# CorruptCore.net
KiCad netlist of a schematic drawn in EAGLE
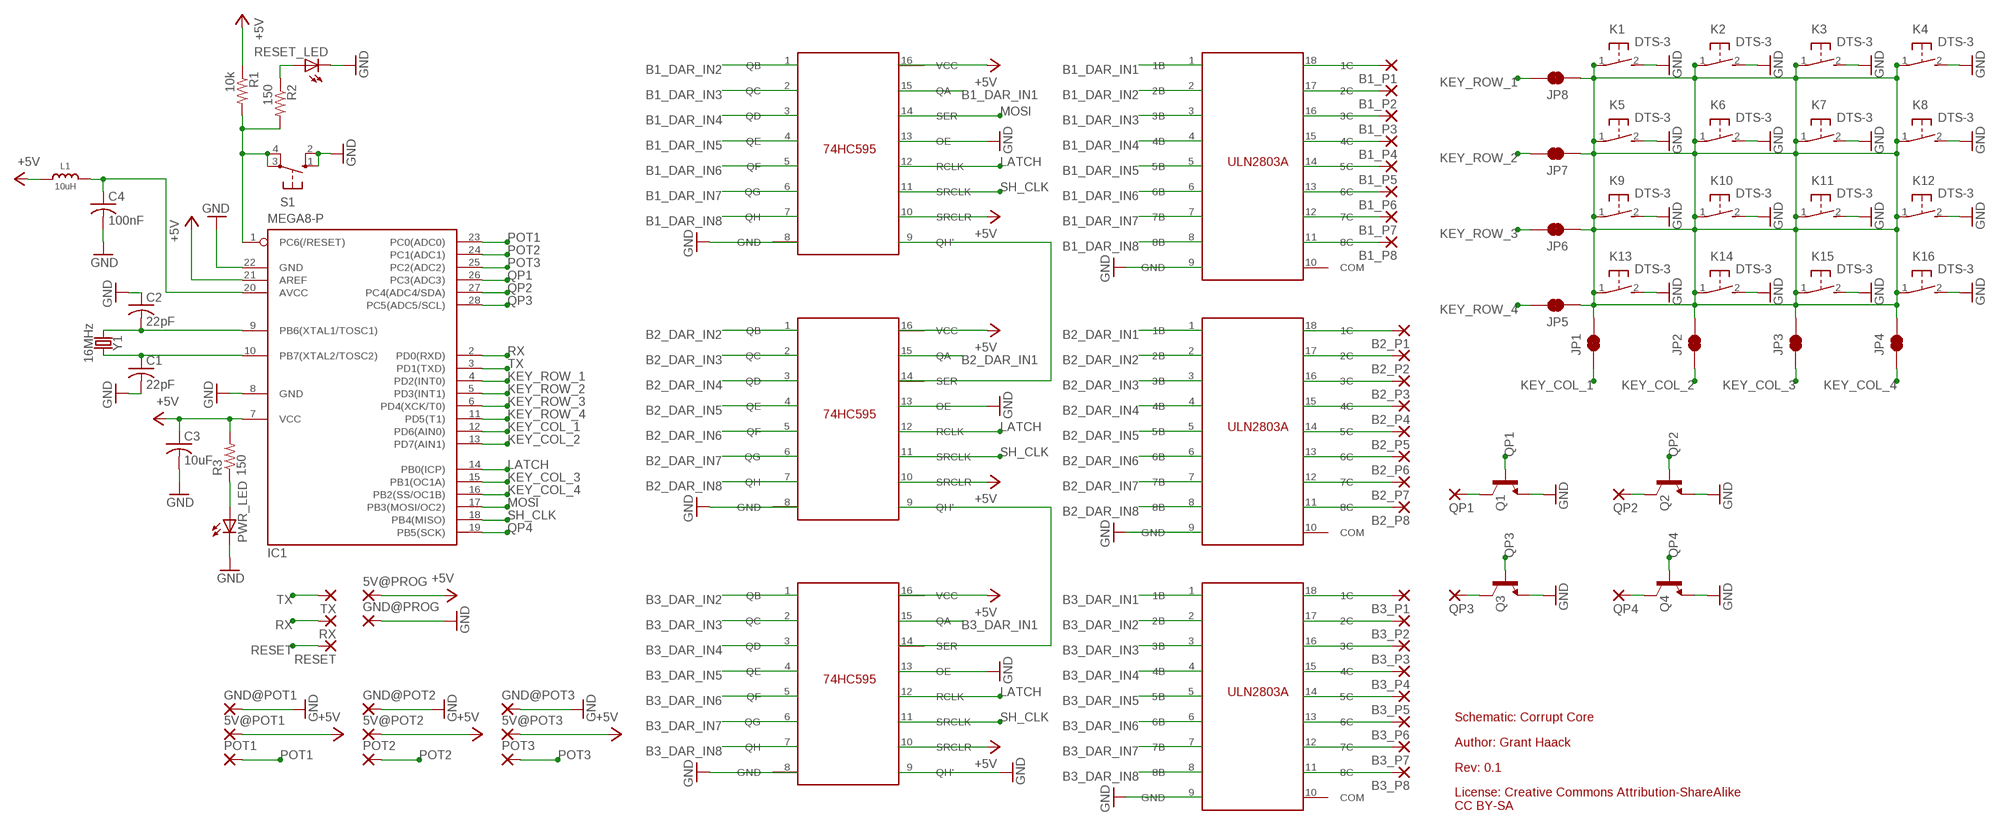
[diagram p0: schematic, sheet 1]

(export (version "E")
  (design (tool "Eeschema 10.0.6"))
  (components
    (comp (ref "5V@POT1")
      (value "2,54/1,1")
      (footprint "eagle-import:2,54_1,1")
      (libsource (lib "eagle-import") (part "2,54/1,1"))
    )
    (comp (ref "5V@POT2")
      (value "2,54/1,1")
      (footprint "eagle-import:2,54_1,1")
      (libsource (lib "eagle-import") (part "2,54/1,1"))
    )
    (comp (ref "5V@POT3")
      (value "2,54/1,1")
      (footprint "eagle-import:2,54_1,1")
      (libsource (lib "eagle-import") (part "2,54/1,1"))
    )
    (comp (ref "5V@PROG")
      (value "2,54/1,1")
      (footprint "eagle-import:2,54_1,1")
      (libsource (lib "eagle-import") (part "2,54/1,1"))
    )
    (comp (ref "B1_P1")
      (value "2,54/1,1")
      (footprint "eagle-import:2,54_1,1")
      (libsource (lib "eagle-import") (part "2,54/1,1"))
    )
    (comp (ref "B1_P2")
      (value "2,54/1,1")
      (footprint "eagle-import:2,54_1,1")
      (libsource (lib "eagle-import") (part "2,54/1,1"))
    )
    (comp (ref "B1_P3")
      (value "2,54/1,1")
      (footprint "eagle-import:2,54_1,1")
      (libsource (lib "eagle-import") (part "2,54/1,1"))
    )
    (comp (ref "B1_P4")
      (value "2,54/1,1")
      (footprint "eagle-import:2,54_1,1")
      (libsource (lib "eagle-import") (part "2,54/1,1"))
    )
    (comp (ref "B1_P5")
      (value "2,54/1,1")
      (footprint "eagle-import:2,54_1,1")
      (libsource (lib "eagle-import") (part "2,54/1,1"))
    )
    (comp (ref "B1_P6")
      (value "2,54/1,1")
      (footprint "eagle-import:2,54_1,1")
      (libsource (lib "eagle-import") (part "2,54/1,1"))
    )
    (comp (ref "B1_P7")
      (value "2,54/1,1")
      (footprint "eagle-import:2,54_1,1")
      (libsource (lib "eagle-import") (part "2,54/1,1"))
    )
    (comp (ref "B1_P8")
      (value "2,54/1,1")
      (footprint "eagle-import:2,54_1,1")
      (libsource (lib "eagle-import") (part "2,54/1,1"))
    )
    (comp (ref "B2_P1")
      (value "2,54/1,1")
      (footprint "eagle-import:2,54_1,1")
      (libsource (lib "eagle-import") (part "2,54/1,1"))
    )
    (comp (ref "B2_P2")
      (value "2,54/1,1")
      (footprint "eagle-import:2,54_1,1")
      (libsource (lib "eagle-import") (part "2,54/1,1"))
    )
    (comp (ref "B2_P3")
      (value "2,54/1,1")
      (footprint "eagle-import:2,54_1,1")
      (libsource (lib "eagle-import") (part "2,54/1,1"))
    )
    (comp (ref "B2_P4")
      (value "2,54/1,1")
      (footprint "eagle-import:2,54_1,1")
      (libsource (lib "eagle-import") (part "2,54/1,1"))
    )
    (comp (ref "B2_P5")
      (value "2,54/1,1")
      (footprint "eagle-import:2,54_1,1")
      (libsource (lib "eagle-import") (part "2,54/1,1"))
    )
    (comp (ref "B2_P6")
      (value "2,54/1,1")
      (footprint "eagle-import:2,54_1,1")
      (libsource (lib "eagle-import") (part "2,54/1,1"))
    )
    (comp (ref "B2_P7")
      (value "2,54/1,1")
      (footprint "eagle-import:2,54_1,1")
      (libsource (lib "eagle-import") (part "2,54/1,1"))
    )
    (comp (ref "B2_P8")
      (value "2,54/1,1")
      (footprint "eagle-import:2,54_1,1")
      (libsource (lib "eagle-import") (part "2,54/1,1"))
    )
    (comp (ref "B3_P1")
      (value "2,54/1,1")
      (footprint "eagle-import:2,54_1,1")
      (libsource (lib "eagle-import") (part "2,54/1,1"))
    )
    (comp (ref "B3_P2")
      (value "2,54/1,1")
      (footprint "eagle-import:2,54_1,1")
      (libsource (lib "eagle-import") (part "2,54/1,1"))
    )
    (comp (ref "B3_P3")
      (value "2,54/1,1")
      (footprint "eagle-import:2,54_1,1")
      (libsource (lib "eagle-import") (part "2,54/1,1"))
    )
    (comp (ref "B3_P4")
      (value "2,54/1,1")
      (footprint "eagle-import:2,54_1,1")
      (libsource (lib "eagle-import") (part "2,54/1,1"))
    )
    (comp (ref "B3_P5")
      (value "2,54/1,1")
      (footprint "eagle-import:2,54_1,1")
      (libsource (lib "eagle-import") (part "2,54/1,1"))
    )
    (comp (ref "B3_P6")
      (value "2,54/1,1")
      (footprint "eagle-import:2,54_1,1")
      (libsource (lib "eagle-import") (part "2,54/1,1"))
    )
    (comp (ref "B3_P7")
      (value "2,54/1,1")
      (footprint "eagle-import:2,54_1,1")
      (libsource (lib "eagle-import") (part "2,54/1,1"))
    )
    (comp (ref "B3_P8")
      (value "2,54/1,1")
      (footprint "eagle-import:2,54_1,1")
      (libsource (lib "eagle-import") (part "2,54/1,1"))
    )
    (comp (ref "C1")
      (value "22pF")
      (footprint "eagle-import:C0805")
      (libsource (lib "eagle-import") (part "C-USC0805"))
    )
    (comp (ref "C2")
      (value "22pF")
      (footprint "eagle-import:C0805")
      (libsource (lib "eagle-import") (part "C-USC0805"))
    )
    (comp (ref "C3")
      (value "10uF")
      (footprint "eagle-import:C0805")
      (libsource (lib "eagle-import") (part "C-USC0805"))
    )
    (comp (ref "C4")
      (value "100nF")
      (footprint "eagle-import:C0805")
      (libsource (lib "eagle-import") (part "C-USC0805"))
    )
    (comp (ref "GND@POT1")
      (value "2,54/1,1")
      (footprint "eagle-import:2,54_1,1")
      (libsource (lib "eagle-import") (part "2,54/1,1"))
    )
    (comp (ref "GND@POT2")
      (value "2,54/1,1")
      (footprint "eagle-import:2,54_1,1")
      (libsource (lib "eagle-import") (part "2,54/1,1"))
    )
    (comp (ref "GND@POT3")
      (value "2,54/1,1")
      (footprint "eagle-import:2,54_1,1")
      (libsource (lib "eagle-import") (part "2,54/1,1"))
    )
    (comp (ref "GND@PROG")
      (value "2,54/1,1")
      (footprint "eagle-import:2,54_1,1")
      (libsource (lib "eagle-import") (part "2,54/1,1"))
    )
    (comp (ref "IC1")
      (value "MEGA8-P")
      (footprint "eagle-import:DIL28-3")
      (libsource (lib "eagle-import") (part "MEGA8-P"))
    )
    (comp (ref "JP1")
      (value "JUMPER-SMT_2_NC_TRACE_NO-SILK")
      (footprint "eagle-import:SMT-JUMPER_2_NC_TRACE_NO-SILK")
      (libsource (lib "eagle-import") (part "JUMPER-SMT_2_NC_TRACE_NO-SILK"))
    )
    (comp (ref "JP2")
      (value "JUMPER-SMT_2_NC_TRACE_NO-SILK")
      (footprint "eagle-import:SMT-JUMPER_2_NC_TRACE_NO-SILK")
      (libsource (lib "eagle-import") (part "JUMPER-SMT_2_NC_TRACE_NO-SILK"))
    )
    (comp (ref "JP3")
      (value "JUMPER-SMT_2_NC_TRACE_NO-SILK")
      (footprint "eagle-import:SMT-JUMPER_2_NC_TRACE_NO-SILK")
      (libsource (lib "eagle-import") (part "JUMPER-SMT_2_NC_TRACE_NO-SILK"))
    )
    (comp (ref "JP4")
      (value "JUMPER-SMT_2_NC_TRACE_NO-SILK")
      (footprint "eagle-import:SMT-JUMPER_2_NC_TRACE_NO-SILK")
      (libsource (lib "eagle-import") (part "JUMPER-SMT_2_NC_TRACE_NO-SILK"))
    )
    (comp (ref "JP5")
      (value "JUMPER-SMT_2_NC_TRACE_NO-SILK")
      (footprint "eagle-import:SMT-JUMPER_2_NC_TRACE_NO-SILK")
      (libsource (lib "eagle-import") (part "JUMPER-SMT_2_NC_TRACE_NO-SILK"))
    )
    (comp (ref "JP6")
      (value "JUMPER-SMT_2_NC_TRACE_NO-SILK")
      (footprint "eagle-import:SMT-JUMPER_2_NC_TRACE_NO-SILK")
      (libsource (lib "eagle-import") (part "JUMPER-SMT_2_NC_TRACE_NO-SILK"))
    )
    (comp (ref "JP7")
      (value "JUMPER-SMT_2_NC_TRACE_NO-SILK")
      (footprint "eagle-import:SMT-JUMPER_2_NC_TRACE_NO-SILK")
      (libsource (lib "eagle-import") (part "JUMPER-SMT_2_NC_TRACE_NO-SILK"))
    )
    (comp (ref "JP8")
      (value "JUMPER-SMT_2_NC_TRACE_NO-SILK")
      (footprint "eagle-import:SMT-JUMPER_2_NC_TRACE_NO-SILK")
      (libsource (lib "eagle-import") (part "JUMPER-SMT_2_NC_TRACE_NO-SILK"))
    )
    (comp (ref "K1")
      (value "DTS-3")
      (footprint "eagle-import:DTS-3")
      (libsource (lib "eagle-import") (part "DTS-3"))
    )
    (comp (ref "K2")
      (value "DTS-3")
      (footprint "eagle-import:DTS-3")
      (libsource (lib "eagle-import") (part "DTS-3"))
    )
    (comp (ref "K3")
      (value "DTS-3")
      (footprint "eagle-import:DTS-3")
      (libsource (lib "eagle-import") (part "DTS-3"))
    )
    (comp (ref "K4")
      (value "DTS-3")
      (footprint "eagle-import:DTS-3")
      (libsource (lib "eagle-import") (part "DTS-3"))
    )
    (comp (ref "K5")
      (value "DTS-3")
      (footprint "eagle-import:DTS-3")
      (libsource (lib "eagle-import") (part "DTS-3"))
    )
    (comp (ref "K6")
      (value "DTS-3")
      (footprint "eagle-import:DTS-3")
      (libsource (lib "eagle-import") (part "DTS-3"))
    )
    (comp (ref "K7")
      (value "DTS-3")
      (footprint "eagle-import:DTS-3")
      (libsource (lib "eagle-import") (part "DTS-3"))
    )
    (comp (ref "K8")
      (value "DTS-3")
      (footprint "eagle-import:DTS-3")
      (libsource (lib "eagle-import") (part "DTS-3"))
    )
    (comp (ref "K9")
      (value "DTS-3")
      (footprint "eagle-import:DTS-3")
      (libsource (lib "eagle-import") (part "DTS-3"))
    )
    (comp (ref "K10")
      (value "DTS-3")
      (footprint "eagle-import:DTS-3")
      (libsource (lib "eagle-import") (part "DTS-3"))
    )
    (comp (ref "K11")
      (value "DTS-3")
      (footprint "eagle-import:DTS-3")
      (libsource (lib "eagle-import") (part "DTS-3"))
    )
    (comp (ref "K12")
      (value "DTS-3")
      (footprint "eagle-import:DTS-3")
      (libsource (lib "eagle-import") (part "DTS-3"))
    )
    (comp (ref "K13")
      (value "DTS-3")
      (footprint "eagle-import:DTS-3")
      (libsource (lib "eagle-import") (part "DTS-3"))
    )
    (comp (ref "K14")
      (value "DTS-3")
      (footprint "eagle-import:DTS-3")
      (libsource (lib "eagle-import") (part "DTS-3"))
    )
    (comp (ref "K15")
      (value "DTS-3")
      (footprint "eagle-import:DTS-3")
      (libsource (lib "eagle-import") (part "DTS-3"))
    )
    (comp (ref "K16")
      (value "DTS-3")
      (footprint "eagle-import:DTS-3")
      (libsource (lib "eagle-import") (part "DTS-3"))
    )
    (comp (ref "L1")
      (value "10uH")
      (footprint "eagle-import:MICROBUILDER__0805")
      (libsource (lib "eagle-import") (part "MICROBUILDER_INDUCTOR_0805"))
    )
    (comp (ref "POT1")
      (value "2,54/1,1")
      (footprint "eagle-import:2,54_1,1")
      (libsource (lib "eagle-import") (part "2,54/1,1"))
    )
    (comp (ref "POT2")
      (value "2,54/1,1")
      (footprint "eagle-import:2,54_1,1")
      (libsource (lib "eagle-import") (part "2,54/1,1"))
    )
    (comp (ref "POT3")
      (value "2,54/1,1")
      (footprint "eagle-import:2,54_1,1")
      (libsource (lib "eagle-import") (part "2,54/1,1"))
    )
    (comp (ref "PWR_LED")
      (value "LEDCHIPLED_0603")
      (footprint "eagle-import:CHIPLED_0603")
      (libsource (lib "eagle-import") (part "LEDCHIPLED_0603"))
    )
    (comp (ref "Q1")
      (value "TRANS_NPN-MMBTA42")
      (footprint "eagle-import:SOT23-3")
      (libsource (lib "eagle-import") (part "TRANS_NPN-MMBTA42"))
    )
    (comp (ref "Q2")
      (value "TRANS_NPN-MMBTA42")
      (footprint "eagle-import:SOT23-3")
      (libsource (lib "eagle-import") (part "TRANS_NPN-MMBTA42"))
    )
    (comp (ref "Q3")
      (value "TRANS_NPN-MMBTA42")
      (footprint "eagle-import:SOT23-3")
      (libsource (lib "eagle-import") (part "TRANS_NPN-MMBTA42"))
    )
    (comp (ref "Q4")
      (value "TRANS_NPN-MMBTA42")
      (footprint "eagle-import:SOT23-3")
      (libsource (lib "eagle-import") (part "TRANS_NPN-MMBTA42"))
    )
    (comp (ref "QP1")
      (value "2,54/1,1")
      (footprint "eagle-import:2,54_1,1")
      (libsource (lib "eagle-import") (part "2,54/1,1"))
    )
    (comp (ref "QP2")
      (value "2,54/1,1")
      (footprint "eagle-import:2,54_1,1")
      (libsource (lib "eagle-import") (part "2,54/1,1"))
    )
    (comp (ref "QP3")
      (value "2,54/1,1")
      (footprint "eagle-import:2,54_1,1")
      (libsource (lib "eagle-import") (part "2,54/1,1"))
    )
    (comp (ref "QP4")
      (value "2,54/1,1")
      (footprint "eagle-import:2,54_1,1")
      (libsource (lib "eagle-import") (part "2,54/1,1"))
    )
    (comp (ref "R1")
      (value "10k")
      (footprint "eagle-import:R0805")
      (libsource (lib "eagle-import") (part "R-US_R0805"))
    )
    (comp (ref "R2")
      (value "150")
      (footprint "eagle-import:R0805")
      (libsource (lib "eagle-import") (part "R-US_R0805"))
    )
    (comp (ref "R3")
      (value "150")
      (footprint "eagle-import:R0805")
      (libsource (lib "eagle-import") (part "R-US_R0805"))
    )
    (comp (ref "RESET")
      (value "2,54/1,1")
      (footprint "eagle-import:2,54_1,1")
      (libsource (lib "eagle-import") (part "2,54/1,1"))
    )
    (comp (ref "RESET_LED")
      (value "LEDCHIPLED_0603")
      (footprint "eagle-import:CHIPLED_0603")
      (libsource (lib "eagle-import") (part "LEDCHIPLED_0603"))
    )
    (comp (ref "RX")
      (value "2,54/1,1")
      (footprint "eagle-import:2,54_1,1")
      (libsource (lib "eagle-import") (part "2,54/1,1"))
    )
    (comp (ref "S1")
      (value "10-XX")
      (footprint "eagle-import:B3F-10XX")
      (fields (field (name "MPN") "B3F-1000"))
      (libsource (lib "eagle-import") (part "10-XX"))
    )
    (comp (ref "TX")
      (value "2,54/1,1")
      (footprint "eagle-import:2,54_1,1")
      (libsource (lib "eagle-import") (part "2,54/1,1"))
    )
    (comp (ref "U$1")
      (value "SN74HC595N")
      (footprint "eagle-import:DIL16")
      (libsource (lib "eagle-import") (part "SN74HC595N"))
    )
    (comp (ref "U$2")
      (value "ULN2803A")
      (footprint "eagle-import:DIL18")
      (libsource (lib "eagle-import") (part "ULN2803A"))
    )
    (comp (ref "U$3")
      (value "SN74HC595N")
      (footprint "eagle-import:DIL16")
      (libsource (lib "eagle-import") (part "SN74HC595N"))
    )
    (comp (ref "U$4")
      (value "ULN2803A")
      (footprint "eagle-import:DIL18")
      (libsource (lib "eagle-import") (part "ULN2803A"))
    )
    (comp (ref "U$5")
      (value "SN74HC595N")
      (footprint "eagle-import:DIL16")
      (libsource (lib "eagle-import") (part "SN74HC595N"))
    )
    (comp (ref "U$6")
      (value "ULN2803A")
      (footprint "eagle-import:DIL18")
      (libsource (lib "eagle-import") (part "ULN2803A"))
    )
    (comp (ref "Y1")
      (value "16MHz")
      (footprint "eagle-import:HC49US")
      (libsource (lib "eagle-import") (part "CRYSTAL-16MHZPTH-HC49US"))
    )
  )
  (nets
    (net (code "1") (name "+5V") (class "Default")
      (node (ref "5V@POT1") (pin "1") (pinfunction "P_1") (pintype "passive"))
      (node (ref "5V@POT2") (pin "1") (pinfunction "P_1") (pintype "passive"))
      (node (ref "5V@POT3") (pin "1") (pinfunction "P_1") (pintype "passive"))
      (node (ref "5V@PROG") (pin "1") (pinfunction "P_1") (pintype "passive"))
      (node (ref "C3") (pin "1") (pinfunction "1_1") (pintype "passive"))
      (node (ref "IC1") (pin "21") (pinfunction "AREF_21") (pintype "passive"))
      (node (ref "IC1") (pin "7") (pinfunction "VCC_7") (pintype "power_in"))
      (node (ref "L1") (pin "1") (pinfunction "1_1") (pintype "passive"))
      (node (ref "R1") (pin "1") (pinfunction "1_1") (pintype "passive"))
      (node (ref "R3") (pin "2") (pinfunction "2_2") (pintype "passive"))
      (node (ref "U$1") (pin "10") (pinfunction "SRCLR_10") (pintype "bidirectional"))
      (node (ref "U$1") (pin "16") (pinfunction "VCC_16") (pintype "bidirectional"))
      (node (ref "U$3") (pin "10") (pinfunction "SRCLR_10") (pintype "bidirectional"))
      (node (ref "U$3") (pin "16") (pinfunction "VCC_16") (pintype "bidirectional"))
      (node (ref "U$5") (pin "10") (pinfunction "SRCLR_10") (pintype "bidirectional"))
      (node (ref "U$5") (pin "16") (pinfunction "VCC_16") (pintype "bidirectional"))
    )
    (net (code "2") (name "/B1_DAR_IN1") (class "Default")
      (node (ref "U$1") (pin "15") (pinfunction "QA_15") (pintype "bidirectional"))
      (node (ref "U$2") (pin "1") (pinfunction "1B_1") (pintype "bidirectional"))
    )
    (net (code "3") (name "/B1_DAR_IN2") (class "Default")
      (node (ref "U$1") (pin "1") (pinfunction "QB_1") (pintype "bidirectional"))
      (node (ref "U$2") (pin "2") (pinfunction "2B_2") (pintype "bidirectional"))
    )
    (net (code "4") (name "/B1_DAR_IN3") (class "Default")
      (node (ref "U$1") (pin "2") (pinfunction "QC_2") (pintype "bidirectional"))
      (node (ref "U$2") (pin "3") (pinfunction "3B_3") (pintype "bidirectional"))
    )
    (net (code "5") (name "/B1_DAR_IN4") (class "Default")
      (node (ref "U$1") (pin "3") (pinfunction "QD_3") (pintype "bidirectional"))
      (node (ref "U$2") (pin "4") (pinfunction "4B_4") (pintype "bidirectional"))
    )
    (net (code "6") (name "/B1_DAR_IN5") (class "Default")
      (node (ref "U$1") (pin "4") (pinfunction "QE_4") (pintype "bidirectional"))
      (node (ref "U$2") (pin "5") (pinfunction "5B_5") (pintype "bidirectional"))
    )
    (net (code "7") (name "/B1_DAR_IN6") (class "Default")
      (node (ref "U$1") (pin "5") (pinfunction "QF_5") (pintype "bidirectional"))
      (node (ref "U$2") (pin "6") (pinfunction "6B_6") (pintype "bidirectional"))
    )
    (net (code "8") (name "/B1_DAR_IN7") (class "Default")
      (node (ref "U$1") (pin "6") (pinfunction "QG_6") (pintype "bidirectional"))
      (node (ref "U$2") (pin "7") (pinfunction "7B_7") (pintype "bidirectional"))
    )
    (net (code "9") (name "/B1_DAR_IN8") (class "Default")
      (node (ref "U$1") (pin "7") (pinfunction "QH_7") (pintype "bidirectional"))
      (node (ref "U$2") (pin "8") (pinfunction "8B_8") (pintype "bidirectional"))
    )
    (net (code "10") (name "/B2_DAR_IN1") (class "Default")
      (node (ref "U$3") (pin "15") (pinfunction "QA_15") (pintype "bidirectional"))
      (node (ref "U$4") (pin "1") (pinfunction "1B_1") (pintype "bidirectional"))
    )
    (net (code "11") (name "/B2_DAR_IN2") (class "Default")
      (node (ref "U$3") (pin "1") (pinfunction "QB_1") (pintype "bidirectional"))
      (node (ref "U$4") (pin "2") (pinfunction "2B_2") (pintype "bidirectional"))
    )
    (net (code "12") (name "/B2_DAR_IN3") (class "Default")
      (node (ref "U$3") (pin "2") (pinfunction "QC_2") (pintype "bidirectional"))
      (node (ref "U$4") (pin "3") (pinfunction "3B_3") (pintype "bidirectional"))
    )
    (net (code "13") (name "/B2_DAR_IN4") (class "Default")
      (node (ref "U$3") (pin "3") (pinfunction "QD_3") (pintype "bidirectional"))
      (node (ref "U$4") (pin "4") (pinfunction "4B_4") (pintype "bidirectional"))
    )
    (net (code "14") (name "/B2_DAR_IN5") (class "Default")
      (node (ref "U$3") (pin "4") (pinfunction "QE_4") (pintype "bidirectional"))
      (node (ref "U$4") (pin "5") (pinfunction "5B_5") (pintype "bidirectional"))
    )
    (net (code "15") (name "/B2_DAR_IN6") (class "Default")
      (node (ref "U$3") (pin "5") (pinfunction "QF_5") (pintype "bidirectional"))
      (node (ref "U$4") (pin "6") (pinfunction "6B_6") (pintype "bidirectional"))
    )
    (net (code "16") (name "/B2_DAR_IN7") (class "Default")
      (node (ref "U$3") (pin "6") (pinfunction "QG_6") (pintype "bidirectional"))
      (node (ref "U$4") (pin "7") (pinfunction "7B_7") (pintype "bidirectional"))
    )
    (net (code "17") (name "/B2_DAR_IN8") (class "Default")
      (node (ref "U$3") (pin "7") (pinfunction "QH_7") (pintype "bidirectional"))
      (node (ref "U$4") (pin "8") (pinfunction "8B_8") (pintype "bidirectional"))
    )
    (net (code "18") (name "/B3_DAR_IN1") (class "Default")
      (node (ref "U$5") (pin "15") (pinfunction "QA_15") (pintype "bidirectional"))
      (node (ref "U$6") (pin "1") (pinfunction "1B_1") (pintype "bidirectional"))
    )
    (net (code "19") (name "/B3_DAR_IN2") (class "Default")
      (node (ref "U$5") (pin "1") (pinfunction "QB_1") (pintype "bidirectional"))
      (node (ref "U$6") (pin "2") (pinfunction "2B_2") (pintype "bidirectional"))
    )
    (net (code "20") (name "/B3_DAR_IN3") (class "Default")
      (node (ref "U$5") (pin "2") (pinfunction "QC_2") (pintype "bidirectional"))
      (node (ref "U$6") (pin "3") (pinfunction "3B_3") (pintype "bidirectional"))
    )
    (net (code "21") (name "/B3_DAR_IN4") (class "Default")
      (node (ref "U$5") (pin "3") (pinfunction "QD_3") (pintype "bidirectional"))
      (node (ref "U$6") (pin "4") (pinfunction "4B_4") (pintype "bidirectional"))
    )
    (net (code "22") (name "/B3_DAR_IN5") (class "Default")
      (node (ref "U$5") (pin "4") (pinfunction "QE_4") (pintype "bidirectional"))
      (node (ref "U$6") (pin "5") (pinfunction "5B_5") (pintype "bidirectional"))
    )
    (net (code "23") (name "/B3_DAR_IN6") (class "Default")
      (node (ref "U$5") (pin "5") (pinfunction "QF_5") (pintype "bidirectional"))
      (node (ref "U$6") (pin "6") (pinfunction "6B_6") (pintype "bidirectional"))
    )
    (net (code "24") (name "/B3_DAR_IN7") (class "Default")
      (node (ref "U$5") (pin "6") (pinfunction "QG_6") (pintype "bidirectional"))
      (node (ref "U$6") (pin "7") (pinfunction "7B_7") (pintype "bidirectional"))
    )
    (net (code "25") (name "/B3_DAR_IN8") (class "Default")
      (node (ref "U$5") (pin "7") (pinfunction "QH_7") (pintype "bidirectional"))
      (node (ref "U$6") (pin "8") (pinfunction "8B_8") (pintype "bidirectional"))
    )
    (net (code "26") (name "/KEY_COL_1") (class "Default")
      (node (ref "IC1") (pin "12") (pinfunction "PD6(AIN0)_12") (pintype "bidirectional"))
      (node (ref "JP1") (pin "1") (pinfunction "1_1") (pintype "passive"))
    )
    (net (code "27") (name "/KEY_COL_2") (class "Default")
      (node (ref "IC1") (pin "13") (pinfunction "PD7(AIN1)_13") (pintype "bidirectional"))
      (node (ref "JP2") (pin "1") (pinfunction "1_1") (pintype "passive"))
    )
    (net (code "28") (name "/KEY_COL_3") (class "Default")
      (node (ref "IC1") (pin "15") (pinfunction "PB1(OC1A)_15") (pintype "bidirectional"))
      (node (ref "JP3") (pin "1") (pinfunction "1_1") (pintype "passive"))
    )
    (net (code "29") (name "/KEY_COL_4") (class "Default")
      (node (ref "IC1") (pin "16") (pinfunction "PB2(SS/OC1B)_16") (pintype "bidirectional"))
      (node (ref "JP4") (pin "1") (pinfunction "1_1") (pintype "passive"))
    )
    (net (code "30") (name "/KEY_ROW_1") (class "Default")
      (node (ref "IC1") (pin "4") (pinfunction "PD2(INT0)_4") (pintype "bidirectional"))
      (node (ref "JP8") (pin "2") (pinfunction "2_2") (pintype "passive"))
    )
    (net (code "31") (name "/KEY_ROW_2") (class "Default")
      (node (ref "IC1") (pin "5") (pinfunction "PD3(INT1)_5") (pintype "bidirectional"))
      (node (ref "JP7") (pin "2") (pinfunction "2_2") (pintype "passive"))
    )
    (net (code "32") (name "/KEY_ROW_3") (class "Default")
      (node (ref "IC1") (pin "6") (pinfunction "PD4(XCK/T0)_6") (pintype "bidirectional"))
      (node (ref "JP6") (pin "2") (pinfunction "2_2") (pintype "passive"))
    )
    (net (code "33") (name "/KEY_ROW_4") (class "Default")
      (node (ref "IC1") (pin "11") (pinfunction "PD5(T1)_11") (pintype "bidirectional"))
      (node (ref "JP5") (pin "2") (pinfunction "2_2") (pintype "passive"))
    )
    (net (code "34") (name "/LATCH") (class "Default")
      (node (ref "IC1") (pin "14") (pinfunction "PB0(ICP)_14") (pintype "bidirectional"))
      (node (ref "U$1") (pin "12") (pinfunction "RCLK_12") (pintype "bidirectional"))
      (node (ref "U$3") (pin "12") (pinfunction "RCLK_12") (pintype "bidirectional"))
      (node (ref "U$5") (pin "12") (pinfunction "RCLK_12") (pintype "bidirectional"))
    )
    (net (code "35") (name "/MOSI") (class "Default")
      (node (ref "IC1") (pin "17") (pinfunction "PB3(MOSI/OC2)_17") (pintype "bidirectional"))
      (node (ref "U$1") (pin "14") (pinfunction "SER_14") (pintype "bidirectional"))
    )
    (net (code "36") (name "/POT1") (class "Default")
      (node (ref "IC1") (pin "23") (pinfunction "PC0(ADC0)_23") (pintype "bidirectional"))
      (node (ref "POT1") (pin "1") (pinfunction "P_1") (pintype "passive"))
    )
    (net (code "37") (name "/POT2") (class "Default")
      (node (ref "IC1") (pin "24") (pinfunction "PC1(ADC1)_24") (pintype "bidirectional"))
      (node (ref "POT2") (pin "1") (pinfunction "P_1") (pintype "passive"))
    )
    (net (code "38") (name "/POT3") (class "Default")
      (node (ref "IC1") (pin "25") (pinfunction "PC2(ADC2)_25") (pintype "bidirectional"))
      (node (ref "POT3") (pin "1") (pinfunction "P_1") (pintype "passive"))
    )
    (net (code "39") (name "/QP1") (class "Default")
      (node (ref "IC1") (pin "26") (pinfunction "PC3(ADC3)_26") (pintype "bidirectional"))
      (node (ref "Q1") (pin "1") (pinfunction "B_1") (pintype "passive"))
    )
    (net (code "40") (name "/QP2") (class "Default")
      (node (ref "IC1") (pin "27") (pinfunction "PC4(ADC4/SDA)_27") (pintype "bidirectional"))
      (node (ref "Q2") (pin "1") (pinfunction "B_1") (pintype "passive"))
    )
    (net (code "41") (name "/QP3") (class "Default")
      (node (ref "IC1") (pin "28") (pinfunction "PC5(ADC5/SCL)_28") (pintype "bidirectional"))
      (node (ref "Q3") (pin "1") (pinfunction "B_1") (pintype "passive"))
    )
    (net (code "42") (name "/QP4") (class "Default")
      (node (ref "IC1") (pin "19") (pinfunction "PB5(SCK)_19") (pintype "bidirectional"))
      (node (ref "Q4") (pin "1") (pinfunction "B_1") (pintype "passive"))
    )
    (net (code "43") (name "/RESET") (class "Default")
      (node (ref "IC1") (pin "1") (pinfunction "PC6(/RESET)_1") (pintype "bidirectional"))
      (node (ref "R1") (pin "2") (pinfunction "2_2") (pintype "passive"))
      (node (ref "R2") (pin "2") (pinfunction "2_2") (pintype "passive"))
      (node (ref "RESET") (pin "1") (pinfunction "P_1") (pintype "passive"))
      (node (ref "S1") (pin "3") (pinfunction "P_3") (pintype "passive"))
      (node (ref "S1") (pin "4") (pinfunction "P1_4") (pintype "passive"))
    )
    (net (code "44") (name "/RX") (class "Default")
      (node (ref "IC1") (pin "2") (pinfunction "PD0(RXD)_2") (pintype "bidirectional"))
      (node (ref "RX") (pin "1") (pinfunction "P_1") (pintype "passive"))
    )
    (net (code "45") (name "/SH_CLK") (class "Default")
      (node (ref "IC1") (pin "18") (pinfunction "PB4(MISO)_18") (pintype "bidirectional"))
      (node (ref "U$1") (pin "11") (pinfunction "SRCLK_11") (pintype "bidirectional"))
      (node (ref "U$3") (pin "11") (pinfunction "SRCLK_11") (pintype "bidirectional"))
      (node (ref "U$5") (pin "11") (pinfunction "SRCLK_11") (pintype "bidirectional"))
    )
    (net (code "46") (name "/TX") (class "Default")
      (node (ref "IC1") (pin "3") (pinfunction "PD1(TXD)_3") (pintype "bidirectional"))
      (node (ref "TX") (pin "1") (pinfunction "P_1") (pintype "passive"))
    )
    (net (code "47") (name "GND") (class "Default")
      (node (ref "C1") (pin "2") (pinfunction "2_2") (pintype "passive"))
      (node (ref "C2") (pin "1") (pinfunction "1_1") (pintype "passive"))
      (node (ref "C3") (pin "2") (pinfunction "2_2") (pintype "passive"))
      (node (ref "C4") (pin "2") (pinfunction "2_2") (pintype "passive"))
      (node (ref "GND@POT1") (pin "1") (pinfunction "P_1") (pintype "passive"))
      (node (ref "GND@POT2") (pin "1") (pinfunction "P_1") (pintype "passive"))
      (node (ref "GND@POT3") (pin "1") (pinfunction "P_1") (pintype "passive"))
      (node (ref "GND@PROG") (pin "1") (pinfunction "P_1") (pintype "passive"))
      (node (ref "IC1") (pin "22") (pinfunction "GND_22") (pintype "power_in"))
      (node (ref "IC1") (pin "8") (pinfunction "GND_8") (pintype "power_in"))
      (node (ref "K1") (pin "2") (pinfunction "2_2") (pintype "passive"))
      (node (ref "K10") (pin "2") (pinfunction "2_2") (pintype "passive"))
      (node (ref "K11") (pin "2") (pinfunction "2_2") (pintype "passive"))
      (node (ref "K12") (pin "2") (pinfunction "2_2") (pintype "passive"))
      (node (ref "K13") (pin "2") (pinfunction "2_2") (pintype "passive"))
      (node (ref "K14") (pin "2") (pinfunction "2_2") (pintype "passive"))
      (node (ref "K15") (pin "2") (pinfunction "2_2") (pintype "passive"))
      (node (ref "K16") (pin "2") (pinfunction "2_2") (pintype "passive"))
      (node (ref "K2") (pin "2") (pinfunction "2_2") (pintype "passive"))
      (node (ref "K3") (pin "2") (pinfunction "2_2") (pintype "passive"))
      (node (ref "K4") (pin "2") (pinfunction "2_2") (pintype "passive"))
      (node (ref "K5") (pin "2") (pinfunction "2_2") (pintype "passive"))
      (node (ref "K6") (pin "2") (pinfunction "2_2") (pintype "passive"))
      (node (ref "K7") (pin "2") (pinfunction "2_2") (pintype "passive"))
      (node (ref "K8") (pin "2") (pinfunction "2_2") (pintype "passive"))
      (node (ref "K9") (pin "2") (pinfunction "2_2") (pintype "passive"))
      (node (ref "PWR_LED") (pin "C") (pinfunction "C_C") (pintype "passive"))
      (node (ref "Q1") (pin "2") (pinfunction "E_2") (pintype "passive"))
      (node (ref "Q2") (pin "2") (pinfunction "E_2") (pintype "passive"))
      (node (ref "Q3") (pin "2") (pinfunction "E_2") (pintype "passive"))
      (node (ref "Q4") (pin "2") (pinfunction "E_2") (pintype "passive"))
      (node (ref "RESET_LED") (pin "C") (pinfunction "C_C") (pintype "passive"))
      (node (ref "S1") (pin "1") (pinfunction "S_1") (pintype "passive"))
      (node (ref "S1") (pin "2") (pinfunction "S1_2") (pintype "passive"))
      (node (ref "U$1") (pin "13") (pinfunction "OE_13") (pintype "bidirectional"))
      (node (ref "U$1") (pin "8") (pinfunction "GND_8") (pintype "bidirectional"))
      (node (ref "U$2") (pin "9") (pinfunction "GND_9") (pintype "bidirectional"))
      (node (ref "U$3") (pin "13") (pinfunction "OE_13") (pintype "bidirectional"))
      (node (ref "U$3") (pin "8") (pinfunction "GND_8") (pintype "bidirectional"))
      (node (ref "U$4") (pin "9") (pinfunction "GND_9") (pintype "bidirectional"))
      (node (ref "U$5") (pin "13") (pinfunction "OE_13") (pintype "bidirectional"))
      (node (ref "U$5") (pin "8") (pinfunction "GND_8") (pintype "bidirectional"))
      (node (ref "U$5") (pin "9") (pinfunction "QH'_9") (pintype "bidirectional"))
      (node (ref "U$6") (pin "9") (pinfunction "GND_9") (pintype "bidirectional"))
    )
    (net (code "48") (name "Net-(B1_P1-P)") (class "Default")
      (node (ref "B1_P1") (pin "1") (pinfunction "P_1") (pintype "passive"))
      (node (ref "U$2") (pin "18") (pinfunction "1C_18") (pintype "bidirectional"))
    )
    (net (code "49") (name "Net-(B1_P2-P)") (class "Default")
      (node (ref "B1_P2") (pin "1") (pinfunction "P_1") (pintype "passive"))
      (node (ref "U$2") (pin "17") (pinfunction "2C_17") (pintype "bidirectional"))
    )
    (net (code "50") (name "Net-(B1_P3-P)") (class "Default")
      (node (ref "B1_P3") (pin "1") (pinfunction "P_1") (pintype "passive"))
      (node (ref "U$2") (pin "16") (pinfunction "3C_16") (pintype "bidirectional"))
    )
    (net (code "51") (name "Net-(B1_P4-P)") (class "Default")
      (node (ref "B1_P4") (pin "1") (pinfunction "P_1") (pintype "passive"))
      (node (ref "U$2") (pin "15") (pinfunction "4C_15") (pintype "bidirectional"))
    )
    (net (code "52") (name "Net-(B1_P5-P)") (class "Default")
      (node (ref "B1_P5") (pin "1") (pinfunction "P_1") (pintype "passive"))
      (node (ref "U$2") (pin "14") (pinfunction "5C_14") (pintype "bidirectional"))
    )
    (net (code "53") (name "Net-(B1_P6-P)") (class "Default")
      (node (ref "B1_P6") (pin "1") (pinfunction "P_1") (pintype "passive"))
      (node (ref "U$2") (pin "13") (pinfunction "6C_13") (pintype "bidirectional"))
    )
    (net (code "54") (name "Net-(B1_P7-P)") (class "Default")
      (node (ref "B1_P7") (pin "1") (pinfunction "P_1") (pintype "passive"))
      (node (ref "U$2") (pin "12") (pinfunction "7C_12") (pintype "bidirectional"))
    )
    (net (code "55") (name "Net-(B1_P8-P)") (class "Default")
      (node (ref "B1_P8") (pin "1") (pinfunction "P_1") (pintype "passive"))
      (node (ref "U$2") (pin "11") (pinfunction "8C_11") (pintype "bidirectional"))
    )
    (net (code "56") (name "Net-(B2_P1-P)") (class "Default")
      (node (ref "B2_P1") (pin "1") (pinfunction "P_1") (pintype "passive"))
      (node (ref "U$4") (pin "18") (pinfunction "1C_18") (pintype "bidirectional"))
    )
    (net (code "57") (name "Net-(B2_P2-P)") (class "Default")
      (node (ref "B2_P2") (pin "1") (pinfunction "P_1") (pintype "passive"))
      (node (ref "U$4") (pin "17") (pinfunction "2C_17") (pintype "bidirectional"))
    )
    (net (code "58") (name "Net-(B2_P3-P)") (class "Default")
      (node (ref "B2_P3") (pin "1") (pinfunction "P_1") (pintype "passive"))
      (node (ref "U$4") (pin "16") (pinfunction "3C_16") (pintype "bidirectional"))
    )
    (net (code "59") (name "Net-(B2_P4-P)") (class "Default")
      (node (ref "B2_P4") (pin "1") (pinfunction "P_1") (pintype "passive"))
      (node (ref "U$4") (pin "15") (pinfunction "4C_15") (pintype "bidirectional"))
    )
    (net (code "60") (name "Net-(B2_P5-P)") (class "Default")
      (node (ref "B2_P5") (pin "1") (pinfunction "P_1") (pintype "passive"))
      (node (ref "U$4") (pin "14") (pinfunction "5C_14") (pintype "bidirectional"))
    )
    (net (code "61") (name "Net-(B2_P6-P)") (class "Default")
      (node (ref "B2_P6") (pin "1") (pinfunction "P_1") (pintype "passive"))
      (node (ref "U$4") (pin "13") (pinfunction "6C_13") (pintype "bidirectional"))
    )
    (net (code "62") (name "Net-(B2_P7-P)") (class "Default")
      (node (ref "B2_P7") (pin "1") (pinfunction "P_1") (pintype "passive"))
      (node (ref "U$4") (pin "12") (pinfunction "7C_12") (pintype "bidirectional"))
    )
    (net (code "63") (name "Net-(B2_P8-P)") (class "Default")
      (node (ref "B2_P8") (pin "1") (pinfunction "P_1") (pintype "passive"))
      (node (ref "U$4") (pin "11") (pinfunction "8C_11") (pintype "bidirectional"))
    )
    (net (code "64") (name "Net-(B3_P1-P)") (class "Default")
      (node (ref "B3_P1") (pin "1") (pinfunction "P_1") (pintype "passive"))
      (node (ref "U$6") (pin "18") (pinfunction "1C_18") (pintype "bidirectional"))
    )
    (net (code "65") (name "Net-(B3_P2-P)") (class "Default")
      (node (ref "B3_P2") (pin "1") (pinfunction "P_1") (pintype "passive"))
      (node (ref "U$6") (pin "17") (pinfunction "2C_17") (pintype "bidirectional"))
    )
    (net (code "66") (name "Net-(B3_P3-P)") (class "Default")
      (node (ref "B3_P3") (pin "1") (pinfunction "P_1") (pintype "passive"))
      (node (ref "U$6") (pin "16") (pinfunction "3C_16") (pintype "bidirectional"))
    )
    (net (code "67") (name "Net-(B3_P4-P)") (class "Default")
      (node (ref "B3_P4") (pin "1") (pinfunction "P_1") (pintype "passive"))
      (node (ref "U$6") (pin "15") (pinfunction "4C_15") (pintype "bidirectional"))
    )
    (net (code "68") (name "Net-(B3_P5-P)") (class "Default")
      (node (ref "B3_P5") (pin "1") (pinfunction "P_1") (pintype "passive"))
      (node (ref "U$6") (pin "14") (pinfunction "5C_14") (pintype "bidirectional"))
    )
    (net (code "69") (name "Net-(B3_P6-P)") (class "Default")
      (node (ref "B3_P6") (pin "1") (pinfunction "P_1") (pintype "passive"))
      (node (ref "U$6") (pin "13") (pinfunction "6C_13") (pintype "bidirectional"))
    )
    (net (code "70") (name "Net-(B3_P7-P)") (class "Default")
      (node (ref "B3_P7") (pin "1") (pinfunction "P_1") (pintype "passive"))
      (node (ref "U$6") (pin "12") (pinfunction "7C_12") (pintype "bidirectional"))
    )
    (net (code "71") (name "Net-(B3_P8-P)") (class "Default")
      (node (ref "B3_P8") (pin "1") (pinfunction "P_1") (pintype "passive"))
      (node (ref "U$6") (pin "11") (pinfunction "8C_11") (pintype "bidirectional"))
    )
    (net (code "72") (name "Net-(IC1-AVCC)") (class "Default")
      (node (ref "C4") (pin "1") (pinfunction "1_1") (pintype "passive"))
      (node (ref "IC1") (pin "20") (pinfunction "AVCC_20") (pintype "power_in"))
      (node (ref "L1") (pin "2") (pinfunction "2_2") (pintype "passive"))
    )
    (net (code "73") (name "Net-(IC1-PB6(XTAL1{slash}TOSC1))") (class "Default")
      (node (ref "C2") (pin "2") (pinfunction "2_2") (pintype "passive"))
      (node (ref "IC1") (pin "9") (pinfunction "PB6(XTAL1/TOSC1)_9") (pintype "bidirectional"))
      (node (ref "Y1") (pin "1") (pinfunction "1_1") (pintype "passive"))
    )
    (net (code "74") (name "Net-(IC1-PB7(XTAL2{slash}TOSC2))") (class "Default")
      (node (ref "C1") (pin "1") (pinfunction "1_1") (pintype "passive"))
      (node (ref "IC1") (pin "10") (pinfunction "PB7(XTAL2/TOSC2)_10") (pintype "bidirectional"))
      (node (ref "Y1") (pin "2") (pinfunction "2_2") (pintype "passive"))
    )
    (net (code "75") (name "Net-(JP1-Pad2)") (class "Default")
      (node (ref "JP1") (pin "2") (pinfunction "2_2") (pintype "passive"))
      (node (ref "JP2") (pin "2") (pinfunction "2_2") (pintype "passive"))
      (node (ref "JP3") (pin "2") (pinfunction "2_2") (pintype "passive"))
      (node (ref "JP4") (pin "2") (pinfunction "2_2") (pintype "passive"))
      (node (ref "JP5") (pin "1") (pinfunction "1_1") (pintype "passive"))
      (node (ref "JP6") (pin "1") (pinfunction "1_1") (pintype "passive"))
      (node (ref "JP7") (pin "1") (pinfunction "1_1") (pintype "passive"))
      (node (ref "JP8") (pin "1") (pinfunction "1_1") (pintype "passive"))
      (node (ref "K1") (pin "1") (pinfunction "1_1") (pintype "passive"))
      (node (ref "K10") (pin "1") (pinfunction "1_1") (pintype "passive"))
      (node (ref "K11") (pin "1") (pinfunction "1_1") (pintype "passive"))
      (node (ref "K12") (pin "1") (pinfunction "1_1") (pintype "passive"))
      (node (ref "K13") (pin "1") (pinfunction "1_1") (pintype "passive"))
      (node (ref "K14") (pin "1") (pinfunction "1_1") (pintype "passive"))
      (node (ref "K15") (pin "1") (pinfunction "1_1") (pintype "passive"))
      (node (ref "K16") (pin "1") (pinfunction "1_1") (pintype "passive"))
      (node (ref "K2") (pin "1") (pinfunction "1_1") (pintype "passive"))
      (node (ref "K3") (pin "1") (pinfunction "1_1") (pintype "passive"))
      (node (ref "K4") (pin "1") (pinfunction "1_1") (pintype "passive"))
      (node (ref "K5") (pin "1") (pinfunction "1_1") (pintype "passive"))
      (node (ref "K6") (pin "1") (pinfunction "1_1") (pintype "passive"))
      (node (ref "K7") (pin "1") (pinfunction "1_1") (pintype "passive"))
      (node (ref "K8") (pin "1") (pinfunction "1_1") (pintype "passive"))
      (node (ref "K9") (pin "1") (pinfunction "1_1") (pintype "passive"))
    )
    (net (code "76") (name "Net-(PWR_LED-PadA)") (class "Default")
      (node (ref "PWR_LED") (pin "A") (pinfunction "A_A") (pintype "passive"))
      (node (ref "R3") (pin "1") (pinfunction "1_1") (pintype "passive"))
    )
    (net (code "77") (name "Net-(Q1-C)") (class "Default")
      (node (ref "Q1") (pin "3") (pinfunction "C_3") (pintype "passive"))
      (node (ref "QP1") (pin "1") (pinfunction "P_1") (pintype "passive"))
    )
    (net (code "78") (name "Net-(Q2-C)") (class "Default")
      (node (ref "Q2") (pin "3") (pinfunction "C_3") (pintype "passive"))
      (node (ref "QP2") (pin "1") (pinfunction "P_1") (pintype "passive"))
    )
    (net (code "79") (name "Net-(Q3-C)") (class "Default")
      (node (ref "Q3") (pin "3") (pinfunction "C_3") (pintype "passive"))
      (node (ref "QP3") (pin "1") (pinfunction "P_1") (pintype "passive"))
    )
    (net (code "80") (name "Net-(Q4-C)") (class "Default")
      (node (ref "Q4") (pin "3") (pinfunction "C_3") (pintype "passive"))
      (node (ref "QP4") (pin "1") (pinfunction "P_1") (pintype "passive"))
    )
    (net (code "81") (name "Net-(R2-Pad1)") (class "Default")
      (node (ref "R2") (pin "1") (pinfunction "1_1") (pintype "passive"))
      (node (ref "RESET_LED") (pin "A") (pinfunction "A_A") (pintype "passive"))
    )
    (net (code "82") (name "Net-(U$1-QH')") (class "Default")
      (node (ref "U$1") (pin "9") (pinfunction "QH'_9") (pintype "bidirectional"))
      (node (ref "U$3") (pin "14") (pinfunction "SER_14") (pintype "bidirectional"))
    )
    (net (code "83") (name "Net-(U$3-QH')") (class "Default")
      (node (ref "U$3") (pin "9") (pinfunction "QH'_9") (pintype "bidirectional"))
      (node (ref "U$5") (pin "14") (pinfunction "SER_14") (pintype "bidirectional"))
    )
    (net (code "84") (name "unconnected-(U$2-COM-Pad10)") (class "Default")
      (node (ref "U$2") (pin "10") (pinfunction "COM_10") (pintype "bidirectional"))
    )
    (net (code "85") (name "unconnected-(U$4-COM-Pad10)") (class "Default")
      (node (ref "U$4") (pin "10") (pinfunction "COM_10") (pintype "bidirectional"))
    )
    (net (code "86") (name "unconnected-(U$6-COM-Pad10)") (class "Default")
      (node (ref "U$6") (pin "10") (pinfunction "COM_10") (pintype "bidirectional"))
    )
  )
)
